# MIDImike_r2.net
KiCad netlist of a schematic drawn in EAGLE
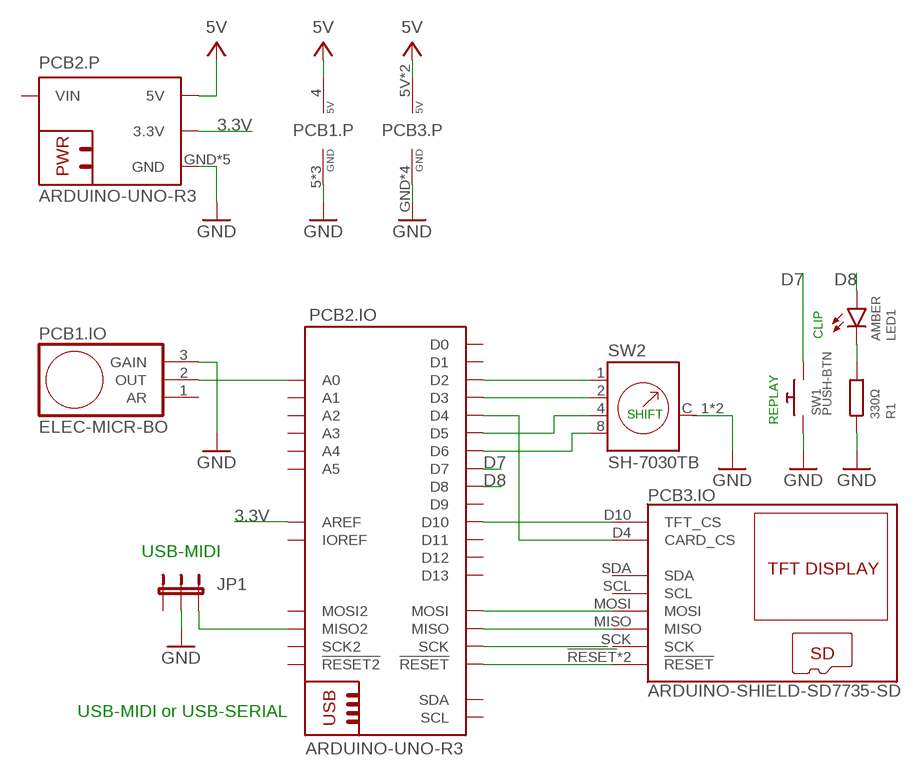
[diagram p0: schematic, sheet 1]

(export (version "E")
  (design (tool "Eeschema 10.0.6"))
  (components
    (comp (ref "JP1")
      (value "JP2E")
      (footprint "eagle-import:JP2")
      (libsource (lib "eagle-import") (part "JP2E"))
    )
    (comp (ref "LED1")
      (value "AMBER")
      (footprint "eagle-import:CHIPLED_0805")
      (libsource (lib "eagle-import") (part "LEDCHIPLED_0805"))
    )
    (comp (ref "PCB1")
      (value "ELEC-MICR-BO")
      (footprint "eagle-import:ELEC_MICR_BREAKOUT")
      (libsource (lib "eagle-import") (part "ELEC-MICR-BO"))
    )
    (comp (ref "PCB2")
      (value "ARDUINO-UNO-R3")
      (footprint "eagle-import:ARDUINO-UNO--R3")
      (libsource (lib "eagle-import") (part "ARDUINO-UNO-R3"))
    )
    (comp (ref "PCB3")
      (value "ARDUINO-SHIELD-SD7735-SD")
      (footprint "eagle-import:ARDIONO-SHIELD")
      (libsource (lib "eagle-import") (part "ARDUINO-SHIELD-SD7735-SD"))
    )
    (comp (ref "R1")
      (value "330Ω")
      (footprint "eagle-import:R0805")
      (fields (field (name "MANF") "Bourns"))
      (libsource (lib "eagle-import") (part "R-EU_R0805"))
    )
    (comp (ref "SW1")
      (value "PUSH-BTN")
      (footprint "eagle-import:TE_1-1825910-4")
      (fields
        (field (name "COMMENT") "1-1825910-4")
        (field (name "DIGI-KEY_PART_NUMBER") "450-1653-ND")
        (field (name "MF") "TE Connectivity")
      )
      (libsource (lib "eagle-import") (part "PUSH-BTN"))
    )
    (comp (ref "SW2")
      (value "SH-7030TB")
      (footprint "eagle-import:SW_RDS-16S-1045-SMT-TR")
      (fields (field (name "MF") "CUI Devices") (field (name "MP") "RDS-16S-1045-SMT-TR"))
      (libsource (lib "eagle-import") (part "SH-7030TB"))
    )
  )
  (nets
    (net (code "1") (name "/3.3V") (class "Default")
      (node (ref "PCB2") (pin "3.3V") (pinfunction "3.3V_3.3V") (pintype "power_in"))
      (node (ref "PCB2") (pin "AREF") (pinfunction "AREF_AREF") (pintype "bidirectional"))
    )
    (net (code "2") (name "/D7") (class "Default")
      (node (ref "PCB2") (pin "D7") (pinfunction "D7_D7") (pintype "bidirectional"))
      (node (ref "SW1") (pin "2") (pinfunction "2_2") (pintype "passive"))
      (node (ref "SW1") (pin "2@1") (pinfunction "2_2@1") (pintype "passive"))
    )
    (net (code "3") (name "/D8") (class "Default")
      (node (ref "LED1") (pin "A") (pinfunction "A_A") (pintype "passive"))
      (node (ref "PCB2") (pin "D8") (pinfunction "D8_D8") (pintype "bidirectional"))
    )
    (net (code "4") (name "/VIN") (class "Default")
      (node (ref "PCB2") (pin "VIN") (pinfunction "VIN_VIN") (pintype "power_in"))
    )
    (net (code "5") (name "5V") (class "Default")
      (node (ref "PCB1") (pin "4") (pinfunction "5V_4") (pintype "passive"))
      (node (ref "PCB2") (pin "5V") (pinfunction "5V_5V") (pintype "power_in"))
      (node (ref "PCB2") (pin "5V@1") (pinfunction "5V_5V@1") (pintype "power_in"))
      (node (ref "PCB2") (pin "5V@2") (pinfunction "5V_5V@2") (pintype "power_in"))
      (node (ref "PCB3") (pin "5V") (pinfunction "5V_5V") (pintype "passive"))
      (node (ref "PCB3") (pin "5V@1") (pinfunction "5V_5V@1") (pintype "passive"))
    )
    (net (code "6") (name "GND") (class "Default")
      (node (ref "JP1") (pin "2") (pinfunction "2_2") (pintype "passive"))
      (node (ref "PCB1") (pin "3") (pinfunction "GAIN_3") (pintype "input"))
      (node (ref "PCB1") (pin "5") (pinfunction "GND_5") (pintype "power_in"))
      (node (ref "PCB1") (pin "P$1") (pinfunction "GND_P$1") (pintype "power_in"))
      (node (ref "PCB1") (pin "P$2") (pinfunction "GND_P$2") (pintype "power_in"))
      (node (ref "PCB2") (pin "GND") (pinfunction "GND_GND") (pintype "power_in"))
      (node (ref "PCB2") (pin "GND@1") (pinfunction "GND_GND@1") (pintype "power_in"))
      (node (ref "PCB2") (pin "GND@2") (pinfunction "GND_GND@2") (pintype "power_in"))
      (node (ref "PCB2") (pin "GND@3") (pinfunction "GND_GND@3") (pintype "power_in"))
      (node (ref "PCB2") (pin "GND@4") (pinfunction "GND_GND@4") (pintype "power_in"))
      (node (ref "PCB3") (pin "GND") (pinfunction "GND_GND") (pintype "power_in"))
      (node (ref "PCB3") (pin "GND@1") (pinfunction "GND_GND@1") (pintype "power_in"))
      (node (ref "PCB3") (pin "GND@2") (pinfunction "GND_GND@2") (pintype "power_in"))
      (node (ref "PCB3") (pin "GND@3") (pinfunction "GND_GND@3") (pintype "power_in"))
      (node (ref "R1") (pin "1") (pinfunction "1_1") (pintype "passive"))
      (node (ref "SW1") (pin "1") (pinfunction "1_1") (pintype "passive"))
      (node (ref "SW1") (pin "1@1") (pinfunction "1_1@1") (pintype "passive"))
      (node (ref "SW2") (pin "C_1") (pinfunction "C_C_1") (pintype "passive"))
      (node (ref "SW2") (pin "C_2") (pinfunction "C_C_2") (pintype "passive"))
    )
    (net (code "7") (name "Net-(JP1-Pad3)") (class "Default")
      (node (ref "JP1") (pin "3") (pinfunction "3_3") (pintype "passive"))
      (node (ref "PCB2") (pin "MISO2") (pinfunction "MISO2_MISO2") (pintype "bidirectional"))
    )
    (net (code "8") (name "Net-(LED1-PadC)") (class "Default")
      (node (ref "LED1") (pin "C") (pinfunction "C_C") (pintype "passive"))
      (node (ref "R1") (pin "2") (pinfunction "2_2") (pintype "passive"))
    )
    (net (code "9") (name "Net-(PCB1A-OUT)") (class "Default")
      (node (ref "PCB1") (pin "2") (pinfunction "OUT_2") (pintype "output"))
      (node (ref "PCB2") (pin "A0") (pinfunction "A0_A0") (pintype "bidirectional"))
    )
    (net (code "10") (name "Net-(PCB2-PadD2)") (class "Default")
      (node (ref "PCB2") (pin "D2") (pinfunction "D2_D2") (pintype "bidirectional"))
      (node (ref "SW2") (pin "1") (pinfunction "1_1") (pintype "passive"))
    )
    (net (code "11") (name "Net-(PCB2-PadD3)") (class "Default")
      (node (ref "PCB2") (pin "D3") (pinfunction "D3_D3") (pintype "bidirectional"))
      (node (ref "SW2") (pin "2") (pinfunction "2_2") (pintype "passive"))
    )
    (net (code "12") (name "Net-(PCB2-PadD5)") (class "Default")
      (node (ref "PCB2") (pin "D5") (pinfunction "D5_D5") (pintype "bidirectional"))
      (node (ref "SW2") (pin "4") (pinfunction "4_4") (pintype "passive"))
    )
    (net (code "13") (name "Net-(PCB2-PadD6)") (class "Default")
      (node (ref "PCB2") (pin "D6") (pinfunction "D6_D6") (pintype "bidirectional"))
      (node (ref "SW2") (pin "8") (pinfunction "8_8") (pintype "passive"))
    )
    (net (code "14") (name "Net-(PCB2-PadMISO)") (class "Default")
      (node (ref "PCB2") (pin "MISO") (pinfunction "MISO_MISO") (pintype "bidirectional"))
      (node (ref "PCB3") (pin "MISO") (pinfunction "MISO_MISO") (pintype "output"))
    )
    (net (code "15") (name "Net-(PCB2-PadMOSI)") (class "Default")
      (node (ref "PCB2") (pin "MOSI") (pinfunction "MOSI_MOSI") (pintype "bidirectional"))
      (node (ref "PCB3") (pin "MOSI") (pinfunction "MOSI_MOSI") (pintype "input"))
    )
    (net (code "16") (name "Net-(PCB2A-~{RESET}-Pad!RESET!)") (class "Default")
      (node (ref "PCB2") (pin "!RESET!") (pinfunction "~{RESET}_!RESET!") (pintype "bidirectional"))
      (node (ref "PCB2") (pin "!RESET!@1") (pinfunction "~{RESET}_!RESET!@1") (pintype "bidirectional"))
      (node (ref "PCB3") (pin "!RESET!") (pinfunction "~{RESET}_!RESET!") (pintype "bidirectional"))
      (node (ref "PCB3") (pin "!RESET!@1") (pinfunction "~{RESET}_!RESET!@1") (pintype "bidirectional"))
    )
    (net (code "17") (name "Net-(PCB3A-CARD_CS)") (class "Default")
      (node (ref "PCB2") (pin "D4") (pinfunction "D4_D4") (pintype "bidirectional"))
      (node (ref "PCB3") (pin "D4") (pinfunction "CARD_CS_D4") (pintype "input"))
    )
    (net (code "18") (name "Net-(PCB3A-TFT_CS)") (class "Default")
      (node (ref "PCB2") (pin "D10") (pinfunction "D10_D10") (pintype "bidirectional"))
      (node (ref "PCB3") (pin "D10") (pinfunction "TFT_CS_D10") (pintype "input"))
    )
    (net (code "19") (name "unconnected-(JP1-Pad1)") (class "Default")
      (node (ref "JP1") (pin "1") (pinfunction "1_1") (pintype "passive"))
    )
    (net (code "20") (name "unconnected-(PCB1A-AR-Pad1)") (class "Default")
      (node (ref "PCB1") (pin "1") (pinfunction "AR_1") (pintype "input"))
    )
    (net (code "21") (name "unconnected-(PCB2-PadA1)") (class "Default")
      (node (ref "PCB2") (pin "A1") (pinfunction "A1_A1") (pintype "bidirectional"))
    )
    (net (code "22") (name "unconnected-(PCB2-PadA2)") (class "Default")
      (node (ref "PCB2") (pin "A2") (pinfunction "A2_A2") (pintype "bidirectional"))
    )
    (net (code "23") (name "unconnected-(PCB2-PadA3)") (class "Default")
      (node (ref "PCB2") (pin "A3") (pinfunction "A3_A3") (pintype "bidirectional"))
    )
    (net (code "24") (name "unconnected-(PCB2-PadA4)") (class "Default")
      (node (ref "PCB2") (pin "A4") (pinfunction "A4_A4") (pintype "bidirectional"))
    )
    (net (code "25") (name "unconnected-(PCB2-PadA5)") (class "Default")
      (node (ref "PCB2") (pin "A5") (pinfunction "A5_A5") (pintype "bidirectional"))
    )
    (net (code "26") (name "unconnected-(PCB2-PadD0)") (class "Default")
      (node (ref "PCB2") (pin "D0") (pinfunction "D0_D0") (pintype "bidirectional"))
    )
    (net (code "27") (name "unconnected-(PCB2-PadD1)") (class "Default")
      (node (ref "PCB2") (pin "D1") (pinfunction "D1_D1") (pintype "bidirectional"))
    )
    (net (code "28") (name "unconnected-(PCB2-PadD9)") (class "Default")
      (node (ref "PCB2") (pin "D9") (pinfunction "D9_D9") (pintype "bidirectional"))
    )
    (net (code "29") (name "unconnected-(PCB2-PadD11)") (class "Default")
      (node (ref "PCB2") (pin "D11") (pinfunction "D11_D11") (pintype "bidirectional"))
    )
    (net (code "30") (name "unconnected-(PCB2-PadD12)") (class "Default")
      (node (ref "PCB2") (pin "D12") (pinfunction "D12_D12") (pintype "bidirectional"))
    )
    (net (code "31") (name "unconnected-(PCB2-PadD13)") (class "Default")
      (node (ref "PCB2") (pin "D13") (pinfunction "D13_D13") (pintype "bidirectional"))
    )
    (net (code "32") (name "unconnected-(PCB2-PadIOREF)") (class "Default")
      (node (ref "PCB2") (pin "IOREF") (pinfunction "IOREF_IOREF") (pintype "bidirectional"))
    )
    (net (code "33") (name "unconnected-(PCB2-PadMOSI2)") (class "Default")
      (node (ref "PCB2") (pin "MOSI2") (pinfunction "MOSI2_MOSI2") (pintype "bidirectional"))
    )
    (net (code "34") (name "unconnected-(PCB2-PadSCK)") (class "Default")
      (node (ref "PCB2") (pin "SCK") (pinfunction "SCK_SCK") (pintype "bidirectional"))
    )
    (net (code "35") (name "unconnected-(PCB2-PadSCK2)") (class "Default")
      (node (ref "PCB2") (pin "SCK2") (pinfunction "SCK2_SCK2") (pintype "bidirectional"))
    )
    (net (code "36") (name "unconnected-(PCB2-PadSCL)") (class "Default")
      (node (ref "PCB2") (pin "SCL") (pinfunction "SCL_SCL") (pintype "bidirectional"))
    )
    (net (code "37") (name "unconnected-(PCB2-PadSDA)") (class "Default")
      (node (ref "PCB2") (pin "SDA") (pinfunction "SDA_SDA") (pintype "bidirectional"))
    )
    (net (code "38") (name "unconnected-(PCB2A-~{RESET2}-Pad!RESET2!)") (class "Default")
      (node (ref "PCB2") (pin "!RESET2!") (pinfunction "~{RESET2}_!RESET2!") (pintype "bidirectional"))
    )
    (net (code "39") (name "unconnected-(PCB3-PadSCK)") (class "Default")
      (node (ref "PCB3") (pin "SCK") (pinfunction "SCK_SCK") (pintype "input"))
    )
    (net (code "40") (name "unconnected-(PCB3-PadSCL)") (class "Default")
      (node (ref "PCB3") (pin "SCL") (pinfunction "SCL_SCL") (pintype "input"))
    )
    (net (code "41") (name "unconnected-(PCB3-PadSDA)") (class "Default")
      (node (ref "PCB3") (pin "SDA") (pinfunction "SDA_SDA") (pintype "bidirectional"))
    )
  )
)
